# Dual_LPF_Schematic.net
KiCad netlist of a schematic drawn in EAGLE
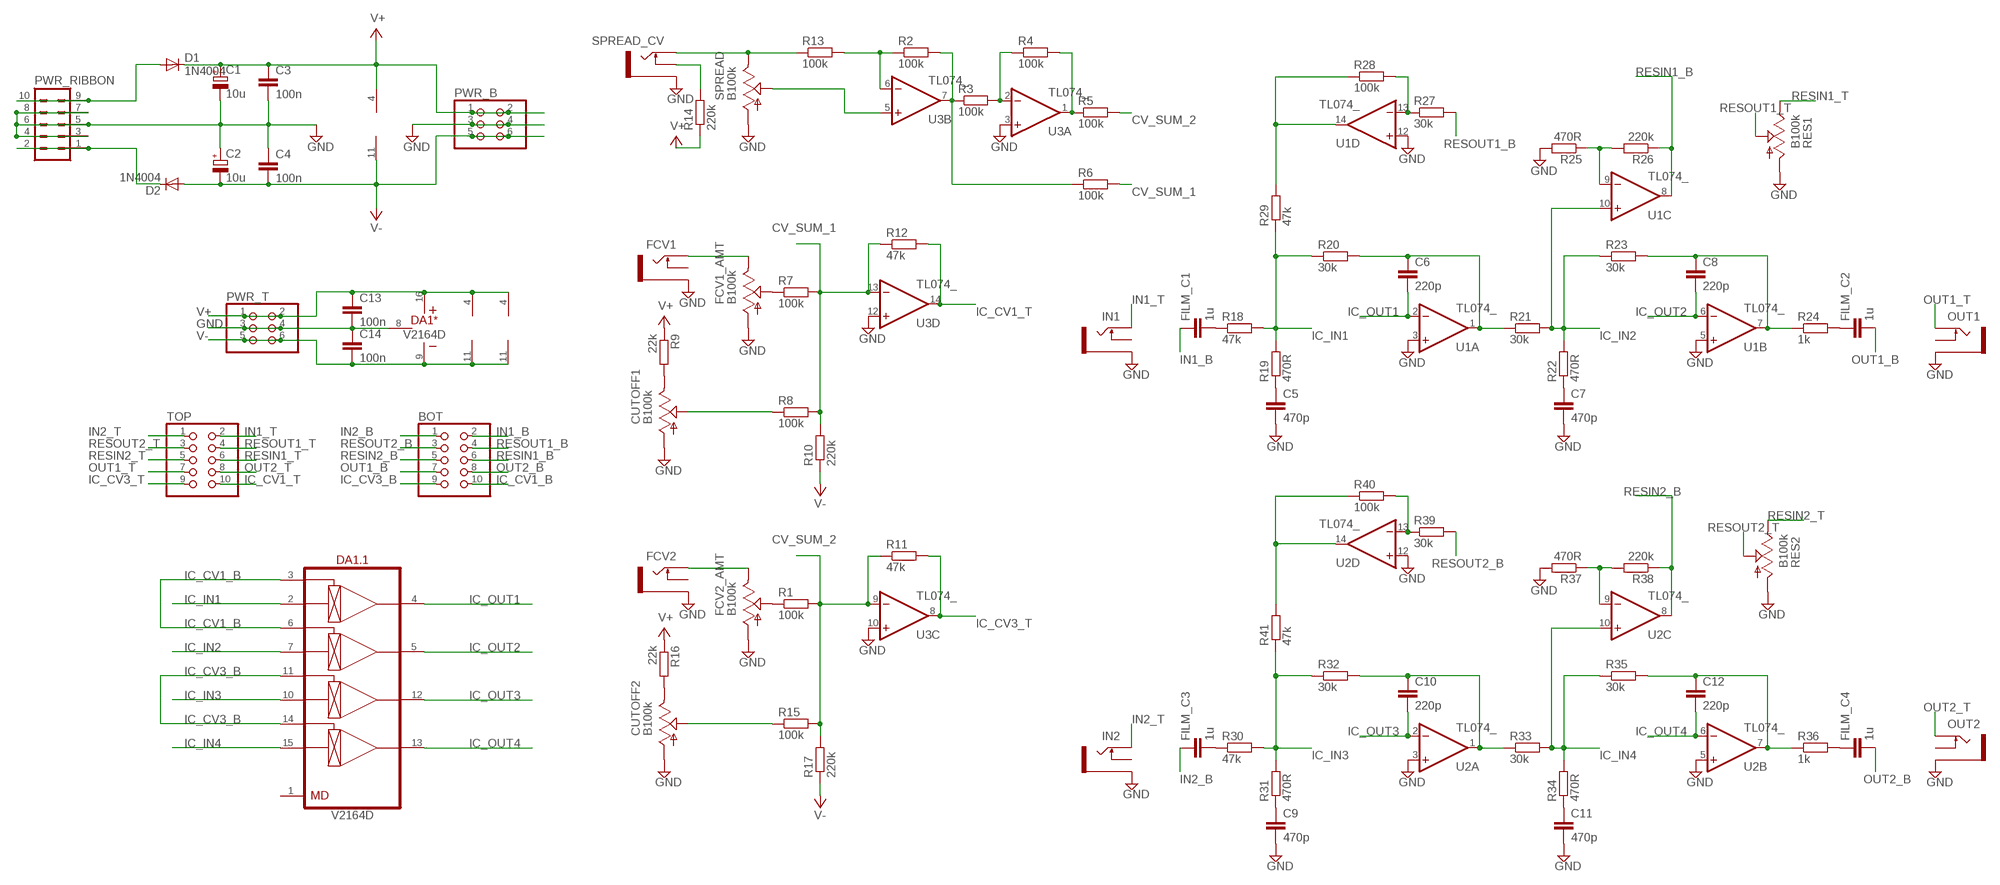
[diagram p0: schematic, sheet 1]

(export (version "E")
  (design (tool "Eeschema 10.0.6"))
  (components
    (comp (ref "BOT")
      (value "PINHD-2X5")
      (footprint "eagle-import:2X05")
      (libsource (lib "eagle-import") (part "PINHD-2X5"))
    )
    (comp (ref "C1")
      (value "10u")
      (footprint "eagle-import:E5-10,5")
      (libsource (lib "eagle-import") (part "CPOL-EUE5-10.5"))
    )
    (comp (ref "C2")
      (value "10u")
      (footprint "eagle-import:E5-10,5")
      (libsource (lib "eagle-import") (part "CPOL-EUE5-10.5"))
    )
    (comp (ref "C3")
      (value "100n")
      (footprint "eagle-import:C050-024X044")
      (libsource (lib "eagle-import") (part "C-EU050-024X044"))
    )
    (comp (ref "C4")
      (value "100n")
      (footprint "eagle-import:C050-024X044")
      (libsource (lib "eagle-import") (part "C-EU050-024X044"))
    )
    (comp (ref "C5")
      (value "470p")
      (footprint "eagle-import:C050-024X044")
      (libsource (lib "eagle-import") (part "C-EU050-024X044"))
    )
    (comp (ref "C6")
      (value "220p")
      (footprint "eagle-import:C050-024X044")
      (libsource (lib "eagle-import") (part "C-EU050-024X044"))
    )
    (comp (ref "C7")
      (value "470p")
      (footprint "eagle-import:C050-024X044")
      (libsource (lib "eagle-import") (part "C-EU050-024X044"))
    )
    (comp (ref "C8")
      (value "220p")
      (footprint "eagle-import:C050-024X044")
      (libsource (lib "eagle-import") (part "C-EU050-024X044"))
    )
    (comp (ref "C9")
      (value "470p")
      (footprint "eagle-import:C050-024X044")
      (libsource (lib "eagle-import") (part "C-EU050-024X044"))
    )
    (comp (ref "C10")
      (value "220p")
      (footprint "eagle-import:C050-024X044")
      (libsource (lib "eagle-import") (part "C-EU050-024X044"))
    )
    (comp (ref "C11")
      (value "470p")
      (footprint "eagle-import:C050-024X044")
      (libsource (lib "eagle-import") (part "C-EU050-024X044"))
    )
    (comp (ref "C12")
      (value "220p")
      (footprint "eagle-import:C050-024X044")
      (libsource (lib "eagle-import") (part "C-EU050-024X044"))
    )
    (comp (ref "C13")
      (value "100n")
      (footprint "eagle-import:C050-024X044")
      (libsource (lib "eagle-import") (part "C-EU050-024X044"))
    )
    (comp (ref "C14")
      (value "100n")
      (footprint "eagle-import:C050-024X044")
      (libsource (lib "eagle-import") (part "C-EU050-024X044"))
    )
    (comp (ref "CUTOFF1")
      (value "B100k")
      (footprint "eagle-import:9MM_SNAP-IN_POT")
      (libsource (lib "eagle-import") (part "9MM_SNAP-IN_POT_"))
    )
    (comp (ref "CUTOFF2")
      (value "B100k")
      (footprint "eagle-import:9MM_SNAP-IN_POT")
      (libsource (lib "eagle-import") (part "9MM_SNAP-IN_POT_"))
    )
    (comp (ref "D1")
      (value "1N4004")
      (footprint "eagle-import:DO41-10")
      (libsource (lib "eagle-import") (part "1N4004"))
    )
    (comp (ref "D2")
      (value "1N4004")
      (footprint "eagle-import:DO41-10")
      (libsource (lib "eagle-import") (part "1N4004"))
    )
    (comp (ref "DA1")
      (value "V2164D")
      (footprint "eagle-import:DIP-16")
      (libsource (lib "eagle-import") (part "V2164D"))
    )
    (comp (ref "FCV1")
      (value "THONKICONNNEW")
      (footprint "eagle-import:WQP-PJ301M-12_JACK")
      (libsource (lib "eagle-import") (part "THONKICONNNEW"))
    )
    (comp (ref "FCV1_AMT")
      (value "B100k")
      (footprint "eagle-import:9MM_SNAP-IN_POT")
      (libsource (lib "eagle-import") (part "9MM_SNAP-IN_POT_"))
    )
    (comp (ref "FCV2")
      (value "THONKICONNNEW")
      (footprint "eagle-import:WQP-PJ301M-12_JACK")
      (libsource (lib "eagle-import") (part "THONKICONNNEW"))
    )
    (comp (ref "FCV2_AMT")
      (value "B100k")
      (footprint "eagle-import:9MM_SNAP-IN_POT")
      (libsource (lib "eagle-import") (part "9MM_SNAP-IN_POT_"))
    )
    (comp (ref "FILM_C1")
      (value "1u")
      (footprint "eagle-import:C050-045X075")
      (libsource (lib "eagle-import") (part "C-EU050-045X075"))
    )
    (comp (ref "FILM_C2")
      (value "1u")
      (footprint "eagle-import:C050-045X075")
      (libsource (lib "eagle-import") (part "C-EU050-045X075"))
    )
    (comp (ref "FILM_C3")
      (value "1u")
      (footprint "eagle-import:C050-045X075")
      (libsource (lib "eagle-import") (part "C-EU050-045X075"))
    )
    (comp (ref "FILM_C4")
      (value "1u")
      (footprint "eagle-import:C050-045X075")
      (libsource (lib "eagle-import") (part "C-EU050-045X075"))
    )
    (comp (ref "IN1")
      (value "THONKICONNNEW")
      (footprint "eagle-import:WQP-PJ301M-12_JACK")
      (libsource (lib "eagle-import") (part "THONKICONNNEW"))
    )
    (comp (ref "IN2")
      (value "THONKICONNNEW")
      (footprint "eagle-import:WQP-PJ301M-12_JACK")
      (libsource (lib "eagle-import") (part "THONKICONNNEW"))
    )
    (comp (ref "OUT1")
      (value "THONKICONNNEW")
      (footprint "eagle-import:WQP-PJ301M-12_JACK")
      (libsource (lib "eagle-import") (part "THONKICONNNEW"))
    )
    (comp (ref "OUT2")
      (value "THONKICONNNEW")
      (footprint "eagle-import:WQP-PJ301M-12_JACK")
      (libsource (lib "eagle-import") (part "THONKICONNNEW"))
    )
    (comp (ref "PWR_B")
      (value "PINHD-2X3")
      (footprint "eagle-import:2X03")
      (libsource (lib "eagle-import") (part "PINHD-2X3"))
    )
    (comp (ref "PWR_RIBBON")
      (value "EURO_POWER_HEADERFAT_PADS")
      (footprint "eagle-import:EURO_PWR_HEADER_FAT")
      (libsource (lib "eagle-import") (part "EURO_POWER_HEADERFAT_PADS"))
    )
    (comp (ref "PWR_T")
      (value "PINHD-2X3")
      (footprint "eagle-import:2X03")
      (libsource (lib "eagle-import") (part "PINHD-2X3"))
    )
    (comp (ref "R1")
      (value "100k")
      (footprint "eagle-import:0207_7")
      (libsource (lib "eagle-import") (part "R-EU_0207/7"))
    )
    (comp (ref "R2")
      (value "100k")
      (footprint "eagle-import:0207_7")
      (libsource (lib "eagle-import") (part "R-EU_0207/7"))
    )
    (comp (ref "R3")
      (value "100k")
      (footprint "eagle-import:0207_7")
      (libsource (lib "eagle-import") (part "R-EU_0207/7"))
    )
    (comp (ref "R4")
      (value "100k")
      (footprint "eagle-import:0207_7")
      (libsource (lib "eagle-import") (part "R-EU_0207/7"))
    )
    (comp (ref "R5")
      (value "100k")
      (footprint "eagle-import:0207_7")
      (libsource (lib "eagle-import") (part "R-EU_0207/7"))
    )
    (comp (ref "R6")
      (value "100k")
      (footprint "eagle-import:0207_7")
      (libsource (lib "eagle-import") (part "R-EU_0207/7"))
    )
    (comp (ref "R7")
      (value "100k")
      (footprint "eagle-import:0207_7")
      (libsource (lib "eagle-import") (part "R-EU_0207/7"))
    )
    (comp (ref "R8")
      (value "100k")
      (footprint "eagle-import:0207_7")
      (libsource (lib "eagle-import") (part "R-EU_0207/7"))
    )
    (comp (ref "R9")
      (value "22k")
      (footprint "eagle-import:0207_7")
      (libsource (lib "eagle-import") (part "R-EU_0207/7"))
    )
    (comp (ref "R10")
      (value "220k")
      (footprint "eagle-import:0207_7")
      (libsource (lib "eagle-import") (part "R-EU_0207/7"))
    )
    (comp (ref "R11")
      (value "47k")
      (footprint "eagle-import:0207_7")
      (libsource (lib "eagle-import") (part "R-EU_0207/7"))
    )
    (comp (ref "R12")
      (value "47k")
      (footprint "eagle-import:0207_7")
      (libsource (lib "eagle-import") (part "R-EU_0207/7"))
    )
    (comp (ref "R13")
      (value "100k")
      (footprint "eagle-import:0207_7")
      (libsource (lib "eagle-import") (part "R-EU_0207/7"))
    )
    (comp (ref "R14")
      (value "220k")
      (footprint "eagle-import:0207_7")
      (libsource (lib "eagle-import") (part "R-EU_0207/7"))
    )
    (comp (ref "R15")
      (value "100k")
      (footprint "eagle-import:0207_7")
      (libsource (lib "eagle-import") (part "R-EU_0207/7"))
    )
    (comp (ref "R16")
      (value "22k")
      (footprint "eagle-import:0207_7")
      (libsource (lib "eagle-import") (part "R-EU_0207/7"))
    )
    (comp (ref "R17")
      (value "220k")
      (footprint "eagle-import:0207_7")
      (libsource (lib "eagle-import") (part "R-EU_0207/7"))
    )
    (comp (ref "R18")
      (value "47k")
      (footprint "eagle-import:0207_7")
      (libsource (lib "eagle-import") (part "R-EU_0207/7"))
    )
    (comp (ref "R19")
      (value "470R")
      (footprint "eagle-import:0207_7")
      (libsource (lib "eagle-import") (part "R-EU_0207/7"))
    )
    (comp (ref "R20")
      (value "30k")
      (footprint "eagle-import:0207_7")
      (libsource (lib "eagle-import") (part "R-EU_0207/7"))
    )
    (comp (ref "R21")
      (value "30k")
      (footprint "eagle-import:0207_7")
      (libsource (lib "eagle-import") (part "R-EU_0207/7"))
    )
    (comp (ref "R22")
      (value "470R")
      (footprint "eagle-import:0207_7")
      (libsource (lib "eagle-import") (part "R-EU_0207/7"))
    )
    (comp (ref "R23")
      (value "30k")
      (footprint "eagle-import:0207_7")
      (libsource (lib "eagle-import") (part "R-EU_0207/7"))
    )
    (comp (ref "R24")
      (value "1k")
      (footprint "eagle-import:0207_7")
      (libsource (lib "eagle-import") (part "R-EU_0207/7"))
    )
    (comp (ref "R25")
      (value "470R")
      (footprint "eagle-import:0207_7")
      (libsource (lib "eagle-import") (part "R-EU_0207/7"))
    )
    (comp (ref "R26")
      (value "220k")
      (footprint "eagle-import:0207_7")
      (libsource (lib "eagle-import") (part "R-EU_0207/7"))
    )
    (comp (ref "R27")
      (value "30k")
      (footprint "eagle-import:0207_7")
      (libsource (lib "eagle-import") (part "R-EU_0207/7"))
    )
    (comp (ref "R28")
      (value "100k")
      (footprint "eagle-import:0207_7")
      (libsource (lib "eagle-import") (part "R-EU_0207/7"))
    )
    (comp (ref "R29")
      (value "47k")
      (footprint "eagle-import:0207_7")
      (libsource (lib "eagle-import") (part "R-EU_0207/7"))
    )
    (comp (ref "R30")
      (value "47k")
      (footprint "eagle-import:0207_7")
      (libsource (lib "eagle-import") (part "R-EU_0207/7"))
    )
    (comp (ref "R31")
      (value "470R")
      (footprint "eagle-import:0207_7")
      (libsource (lib "eagle-import") (part "R-EU_0207/7"))
    )
    (comp (ref "R32")
      (value "30k")
      (footprint "eagle-import:0207_7")
      (libsource (lib "eagle-import") (part "R-EU_0207/7"))
    )
    (comp (ref "R33")
      (value "30k")
      (footprint "eagle-import:0207_7")
      (libsource (lib "eagle-import") (part "R-EU_0207/7"))
    )
    (comp (ref "R34")
      (value "470R")
      (footprint "eagle-import:0207_7")
      (libsource (lib "eagle-import") (part "R-EU_0207/7"))
    )
    (comp (ref "R35")
      (value "30k")
      (footprint "eagle-import:0207_7")
      (libsource (lib "eagle-import") (part "R-EU_0207/7"))
    )
    (comp (ref "R36")
      (value "1k")
      (footprint "eagle-import:0207_7")
      (libsource (lib "eagle-import") (part "R-EU_0207/7"))
    )
    (comp (ref "R37")
      (value "470R")
      (footprint "eagle-import:0207_7")
      (libsource (lib "eagle-import") (part "R-EU_0207/7"))
    )
    (comp (ref "R38")
      (value "220k")
      (footprint "eagle-import:0207_7")
      (libsource (lib "eagle-import") (part "R-EU_0207/7"))
    )
    (comp (ref "R39")
      (value "30k")
      (footprint "eagle-import:0207_7")
      (libsource (lib "eagle-import") (part "R-EU_0207/7"))
    )
    (comp (ref "R40")
      (value "100k")
      (footprint "eagle-import:0207_7")
      (libsource (lib "eagle-import") (part "R-EU_0207/7"))
    )
    (comp (ref "R41")
      (value "47k")
      (footprint "eagle-import:0207_7")
      (libsource (lib "eagle-import") (part "R-EU_0207/7"))
    )
    (comp (ref "RES1")
      (value "B100k")
      (footprint "eagle-import:9MM_SNAP-IN_POT")
      (libsource (lib "eagle-import") (part "9MM_SNAP-IN_POT_"))
    )
    (comp (ref "RES2")
      (value "B100k")
      (footprint "eagle-import:9MM_SNAP-IN_POT")
      (libsource (lib "eagle-import") (part "9MM_SNAP-IN_POT_"))
    )
    (comp (ref "SPREAD")
      (value "B100k")
      (footprint "eagle-import:9MM_SNAP-IN_POT")
      (libsource (lib "eagle-import") (part "9MM_SNAP-IN_POT_"))
    )
    (comp (ref "SPREAD_CV")
      (value "THONKICONNNEW")
      (footprint "eagle-import:WQP-PJ301M-12_JACK")
      (libsource (lib "eagle-import") (part "THONKICONNNEW"))
    )
    (comp (ref "TOP")
      (value "PINHD-2X5")
      (footprint "eagle-import:2X05")
      (libsource (lib "eagle-import") (part "PINHD-2X5"))
    )
    (comp (ref "U1")
      (value "TL074_")
      (footprint "eagle-import:DIL14")
      (libsource (lib "eagle-import") (part "TL074_"))
    )
    (comp (ref "U2")
      (value "TL074_")
      (footprint "eagle-import:DIL14")
      (libsource (lib "eagle-import") (part "TL074_"))
    )
    (comp (ref "U3")
      (value "TL074_")
      (footprint "eagle-import:DIL14")
      (libsource (lib "eagle-import") (part "TL074_"))
    )
  )
  (nets
    (net (code "1") (name "CV_SUM_1") (class "Default")
      (node (ref "R10") (pin "2") (pinfunction "2_2") (pintype "passive"))
      (node (ref "R12") (pin "1") (pinfunction "1_1") (pintype "passive"))
      (node (ref "R6") (pin "2") (pinfunction "2_2") (pintype "passive"))
      (node (ref "R7") (pin "2") (pinfunction "2_2") (pintype "passive"))
      (node (ref "R8") (pin "2") (pinfunction "2_2") (pintype "passive"))
      (node (ref "U3") (pin "13") (pinfunction "-IN_13") (pintype "input"))
    )
    (net (code "2") (name "CV_SUM_2") (class "Default")
      (node (ref "R1") (pin "2") (pinfunction "2_2") (pintype "passive"))
      (node (ref "R11") (pin "1") (pinfunction "1_1") (pintype "passive"))
      (node (ref "R15") (pin "2") (pinfunction "2_2") (pintype "passive"))
      (node (ref "R17") (pin "2") (pinfunction "2_2") (pintype "passive"))
      (node (ref "R5") (pin "2") (pinfunction "2_2") (pintype "passive"))
      (node (ref "U3") (pin "9") (pinfunction "-IN_9") (pintype "input"))
    )
    (net (code "3") (name "GND") (class "Default")
      (node (ref "C1") (pin "-") (pinfunction "-_-") (pintype "passive"))
      (node (ref "C11") (pin "2") (pinfunction "2_2") (pintype "passive"))
      (node (ref "C13") (pin "2") (pinfunction "2_2") (pintype "passive"))
      (node (ref "C14") (pin "1") (pinfunction "1_1") (pintype "passive"))
      (node (ref "C2") (pin "+") (pinfunction "+_+") (pintype "passive"))
      (node (ref "C3") (pin "2") (pinfunction "2_2") (pintype "passive"))
      (node (ref "C4") (pin "1") (pinfunction "1_1") (pintype "passive"))
      (node (ref "C5") (pin "2") (pinfunction "2_2") (pintype "passive"))
      (node (ref "C7") (pin "2") (pinfunction "2_2") (pintype "passive"))
      (node (ref "C9") (pin "2") (pinfunction "2_2") (pintype "passive"))
      (node (ref "CUTOFF1") (pin "1") (pinfunction "A_1") (pintype "passive"))
      (node (ref "CUTOFF2") (pin "1") (pinfunction "A_1") (pintype "passive"))
      (node (ref "DA1") (pin "8") (pinfunction "GND_8") (pintype "power_in"))
      (node (ref "FCV1") (pin "P$3_SLEEVE") (pinfunction "SLEEVE_P$3_SLEEVE") (pintype "passive"))
      (node (ref "FCV1_AMT") (pin "1") (pinfunction "A_1") (pintype "passive"))
      (node (ref "FCV2") (pin "P$3_SLEEVE") (pinfunction "SLEEVE_P$3_SLEEVE") (pintype "passive"))
      (node (ref "FCV2_AMT") (pin "1") (pinfunction "A_1") (pintype "passive"))
      (node (ref "IN1") (pin "P$3_SLEEVE") (pinfunction "SLEEVE_P$3_SLEEVE") (pintype "passive"))
      (node (ref "IN2") (pin "P$3_SLEEVE") (pinfunction "SLEEVE_P$3_SLEEVE") (pintype "passive"))
      (node (ref "OUT1") (pin "P$3_SLEEVE") (pinfunction "SLEEVE_P$3_SLEEVE") (pintype "passive"))
      (node (ref "OUT2") (pin "P$3_SLEEVE") (pinfunction "SLEEVE_P$3_SLEEVE") (pintype "passive"))
      (node (ref "PWR_B") (pin "3") (pinfunction "3_3") (pintype "passive"))
      (node (ref "PWR_B") (pin "4") (pinfunction "4_4") (pintype "passive"))
      (node (ref "PWR_RIBBON") (pin "3") (pinfunction "3_3") (pintype "passive"))
      (node (ref "PWR_RIBBON") (pin "4") (pinfunction "4_4") (pintype "passive"))
      (node (ref "PWR_RIBBON") (pin "5") (pinfunction "5_5") (pintype "passive"))
      (node (ref "PWR_RIBBON") (pin "6") (pinfunction "6_6") (pintype "passive"))
      (node (ref "PWR_RIBBON") (pin "7") (pinfunction "7_7") (pintype "passive"))
      (node (ref "PWR_RIBBON") (pin "8") (pinfunction "8_8") (pintype "passive"))
      (node (ref "PWR_T") (pin "3") (pinfunction "3_3") (pintype "passive"))
      (node (ref "PWR_T") (pin "4") (pinfunction "4_4") (pintype "passive"))
      (node (ref "R25") (pin "2") (pinfunction "2_2") (pintype "passive"))
      (node (ref "R37") (pin "2") (pinfunction "2_2") (pintype "passive"))
      (node (ref "RES1") (pin "1") (pinfunction "A_1") (pintype "passive"))
      (node (ref "RES2") (pin "1") (pinfunction "A_1") (pintype "passive"))
      (node (ref "SPREAD") (pin "1") (pinfunction "A_1") (pintype "passive"))
      (node (ref "SPREAD_CV") (pin "P$3_SLEEVE") (pinfunction "SLEEVE_P$3_SLEEVE") (pintype "passive"))
      (node (ref "U1") (pin "12") (pinfunction "+IN_12") (pintype "input"))
      (node (ref "U1") (pin "3") (pinfunction "+IN_3") (pintype "input"))
      (node (ref "U1") (pin "5") (pinfunction "+IN_5") (pintype "input"))
      (node (ref "U2") (pin "12") (pinfunction "+IN_12") (pintype "input"))
      (node (ref "U2") (pin "3") (pinfunction "+IN_3") (pintype "input"))
      (node (ref "U2") (pin "5") (pinfunction "+IN_5") (pintype "input"))
      (node (ref "U3") (pin "10") (pinfunction "+IN_10") (pintype "input"))
      (node (ref "U3") (pin "12") (pinfunction "+IN_12") (pintype "input"))
      (node (ref "U3") (pin "3") (pinfunction "+IN_3") (pintype "input"))
    )
    (net (code "4") (name "IC_CV1_B") (class "Default")
      (node (ref "BOT") (pin "10") (pinfunction "10_10") (pintype "passive"))
      (node (ref "DA1") (pin "3") (pinfunction "CV1_3") (pintype "input"))
      (node (ref "DA1") (pin "6") (pinfunction "CV2_6") (pintype "input"))
    )
    (net (code "5") (name "IC_CV1_T") (class "Default")
      (node (ref "R12") (pin "2") (pinfunction "2_2") (pintype "passive"))
      (node (ref "TOP") (pin "10") (pinfunction "10_10") (pintype "passive"))
      (node (ref "U3") (pin "14") (pinfunction "OUT_14") (pintype "output"))
    )
    (net (code "6") (name "IC_CV3_B") (class "Default")
      (node (ref "BOT") (pin "9") (pinfunction "9_9") (pintype "passive"))
      (node (ref "DA1") (pin "11") (pinfunction "CV3_11") (pintype "input"))
      (node (ref "DA1") (pin "14") (pinfunction "CV4_14") (pintype "input"))
    )
    (net (code "7") (name "IC_CV3_T") (class "Default")
      (node (ref "R11") (pin "2") (pinfunction "2_2") (pintype "passive"))
      (node (ref "TOP") (pin "9") (pinfunction "9_9") (pintype "passive"))
      (node (ref "U3") (pin "8") (pinfunction "OUT_8") (pintype "output"))
    )
    (net (code "8") (name "IC_IN1") (class "Default")
      (node (ref "DA1") (pin "2") (pinfunction "IN1_2") (pintype "input"))
      (node (ref "R18") (pin "2") (pinfunction "2_2") (pintype "passive"))
      (node (ref "R19") (pin "2") (pinfunction "2_2") (pintype "passive"))
      (node (ref "R20") (pin "1") (pinfunction "1_1") (pintype "passive"))
      (node (ref "R29") (pin "1") (pinfunction "1_1") (pintype "passive"))
    )
    (net (code "9") (name "IC_IN2") (class "Default")
      (node (ref "DA1") (pin "7") (pinfunction "IN2_7") (pintype "input"))
      (node (ref "R21") (pin "2") (pinfunction "2_2") (pintype "passive"))
      (node (ref "R22") (pin "2") (pinfunction "2_2") (pintype "passive"))
      (node (ref "R23") (pin "1") (pinfunction "1_1") (pintype "passive"))
      (node (ref "U1") (pin "10") (pinfunction "+IN_10") (pintype "input"))
    )
    (net (code "10") (name "IC_IN3") (class "Default")
      (node (ref "DA1") (pin "10") (pinfunction "IN3_10") (pintype "input"))
      (node (ref "R30") (pin "2") (pinfunction "2_2") (pintype "passive"))
      (node (ref "R31") (pin "2") (pinfunction "2_2") (pintype "passive"))
      (node (ref "R32") (pin "1") (pinfunction "1_1") (pintype "passive"))
      (node (ref "R41") (pin "1") (pinfunction "1_1") (pintype "passive"))
    )
    (net (code "11") (name "IC_IN4") (class "Default")
      (node (ref "DA1") (pin "15") (pinfunction "IN4_15") (pintype "input"))
      (node (ref "R33") (pin "2") (pinfunction "2_2") (pintype "passive"))
      (node (ref "R34") (pin "2") (pinfunction "2_2") (pintype "passive"))
      (node (ref "R35") (pin "1") (pinfunction "1_1") (pintype "passive"))
      (node (ref "U2") (pin "10") (pinfunction "+IN_10") (pintype "input"))
    )
    (net (code "12") (name "IC_OUT1") (class "Default")
      (node (ref "C6") (pin "2") (pinfunction "2_2") (pintype "passive"))
      (node (ref "DA1") (pin "4") (pinfunction "OUT1_4") (pintype "output"))
      (node (ref "U1") (pin "2") (pinfunction "-IN_2") (pintype "input"))
    )
    (net (code "13") (name "IC_OUT2") (class "Default")
      (node (ref "C8") (pin "2") (pinfunction "2_2") (pintype "passive"))
      (node (ref "DA1") (pin "5") (pinfunction "OUT2_5") (pintype "output"))
      (node (ref "U1") (pin "6") (pinfunction "-IN_6") (pintype "input"))
    )
    (net (code "14") (name "IC_OUT3") (class "Default")
      (node (ref "C10") (pin "2") (pinfunction "2_2") (pintype "passive"))
      (node (ref "DA1") (pin "12") (pinfunction "OUT3_12") (pintype "output"))
      (node (ref "U2") (pin "2") (pinfunction "-IN_2") (pintype "input"))
    )
    (net (code "15") (name "IC_OUT4") (class "Default")
      (node (ref "C12") (pin "2") (pinfunction "2_2") (pintype "passive"))
      (node (ref "DA1") (pin "13") (pinfunction "OUT4_13") (pintype "output"))
      (node (ref "U2") (pin "6") (pinfunction "-IN_6") (pintype "input"))
    )
    (net (code "16") (name "IN1_B") (class "Default")
      (node (ref "BOT") (pin "2") (pinfunction "2_2") (pintype "passive"))
      (node (ref "FILM_C1") (pin "1") (pinfunction "1_1") (pintype "passive"))
    )
    (net (code "17") (name "IN1_T") (class "Default")
      (node (ref "IN1") (pin "P$1_TIP") (pinfunction "TIP_P$1_TIP") (pintype "passive"))
      (node (ref "TOP") (pin "2") (pinfunction "2_2") (pintype "passive"))
    )
    (net (code "18") (name "IN2_B") (class "Default")
      (node (ref "BOT") (pin "1") (pinfunction "1_1") (pintype "passive"))
      (node (ref "FILM_C3") (pin "1") (pinfunction "1_1") (pintype "passive"))
    )
    (net (code "19") (name "IN2_T") (class "Default")
      (node (ref "IN2") (pin "P$1_TIP") (pinfunction "TIP_P$1_TIP") (pintype "passive"))
      (node (ref "TOP") (pin "1") (pinfunction "1_1") (pintype "passive"))
    )
    (net (code "20") (name "Net-(C5-Pad1)") (class "Default")
      (node (ref "C5") (pin "1") (pinfunction "1_1") (pintype "passive"))
      (node (ref "R19") (pin "1") (pinfunction "1_1") (pintype "passive"))
    )
    (net (code "21") (name "Net-(C7-Pad1)") (class "Default")
      (node (ref "C7") (pin "1") (pinfunction "1_1") (pintype "passive"))
      (node (ref "R22") (pin "1") (pinfunction "1_1") (pintype "passive"))
    )
    (net (code "22") (name "Net-(C9-Pad1)") (class "Default")
      (node (ref "C9") (pin "1") (pinfunction "1_1") (pintype "passive"))
      (node (ref "R31") (pin "1") (pinfunction "1_1") (pintype "passive"))
    )
    (net (code "23") (name "Net-(C11-Pad1)") (class "Default")
      (node (ref "C11") (pin "1") (pinfunction "1_1") (pintype "passive"))
      (node (ref "R34") (pin "1") (pinfunction "1_1") (pintype "passive"))
    )
    (net (code "24") (name "Net-(CUTOFF1-E)") (class "Default")
      (node (ref "CUTOFF1") (pin "3") (pinfunction "E_3") (pintype "passive"))
      (node (ref "R9") (pin "2") (pinfunction "2_2") (pintype "passive"))
    )
    (net (code "25") (name "Net-(CUTOFF1-S)") (class "Default")
      (node (ref "CUTOFF1") (pin "2") (pinfunction "S_2") (pintype "passive"))
      (node (ref "R8") (pin "1") (pinfunction "1_1") (pintype "passive"))
    )
    (net (code "26") (name "Net-(CUTOFF2-E)") (class "Default")
      (node (ref "CUTOFF2") (pin "3") (pinfunction "E_3") (pintype "passive"))
      (node (ref "R16") (pin "2") (pinfunction "2_2") (pintype "passive"))
    )
    (net (code "27") (name "Net-(CUTOFF2-S)") (class "Default")
      (node (ref "CUTOFF2") (pin "2") (pinfunction "S_2") (pintype "passive"))
      (node (ref "R15") (pin "1") (pinfunction "1_1") (pintype "passive"))
    )
    (net (code "28") (name "Net-(D1-PadA)") (class "Default")
      (node (ref "D1") (pin "A") (pinfunction "A_A") (pintype "passive"))
      (node (ref "PWR_RIBBON") (pin "10") (pinfunction "10_10") (pintype "passive"))
      (node (ref "PWR_RIBBON") (pin "9") (pinfunction "9_9") (pintype "passive"))
    )
    (net (code "29") (name "Net-(D2-PadC)") (class "Default")
      (node (ref "D2") (pin "C") (pinfunction "C_C") (pintype "passive"))
      (node (ref "PWR_RIBBON") (pin "1") (pinfunction "1_1") (pintype "passive"))
      (node (ref "PWR_RIBBON") (pin "2") (pinfunction "2_2") (pintype "passive"))
    )
    (net (code "30") (name "Net-(FCV1-TIP)") (class "Default")
      (node (ref "FCV1") (pin "P$1_TIP") (pinfunction "TIP_P$1_TIP") (pintype "passive"))
      (node (ref "FCV1_AMT") (pin "3") (pinfunction "E_3") (pintype "passive"))
    )
    (net (code "31") (name "Net-(FCV1_AMT-S)") (class "Default")
      (node (ref "FCV1_AMT") (pin "2") (pinfunction "S_2") (pintype "passive"))
      (node (ref "R7") (pin "1") (pinfunction "1_1") (pintype "passive"))
    )
    (net (code "32") (name "Net-(FCV2-TIP)") (class "Default")
      (node (ref "FCV2") (pin "P$1_TIP") (pinfunction "TIP_P$1_TIP") (pintype "passive"))
      (node (ref "FCV2_AMT") (pin "3") (pinfunction "E_3") (pintype "passive"))
    )
    (net (code "33") (name "Net-(FCV2_AMT-S)") (class "Default")
      (node (ref "FCV2_AMT") (pin "2") (pinfunction "S_2") (pintype "passive"))
      (node (ref "R1") (pin "1") (pinfunction "1_1") (pintype "passive"))
    )
    (net (code "34") (name "Net-(FILM_C1-Pad2)") (class "Default")
      (node (ref "FILM_C1") (pin "2") (pinfunction "2_2") (pintype "passive"))
      (node (ref "R18") (pin "1") (pinfunction "1_1") (pintype "passive"))
    )
    (net (code "35") (name "Net-(FILM_C2-Pad1)") (class "Default")
      (node (ref "FILM_C2") (pin "1") (pinfunction "1_1") (pintype "passive"))
      (node (ref "R24") (pin "2") (pinfunction "2_2") (pintype "passive"))
    )
    (net (code "36") (name "Net-(FILM_C3-Pad2)") (class "Default")
      (node (ref "FILM_C3") (pin "2") (pinfunction "2_2") (pintype "passive"))
      (node (ref "R30") (pin "1") (pinfunction "1_1") (pintype "passive"))
    )
    (net (code "37") (name "Net-(FILM_C4-Pad1)") (class "Default")
      (node (ref "FILM_C4") (pin "1") (pinfunction "1_1") (pintype "passive"))
      (node (ref "R36") (pin "2") (pinfunction "2_2") (pintype "passive"))
    )
    (net (code "38") (name "Net-(SPREAD-E)") (class "Default")
      (node (ref "R13") (pin "1") (pinfunction "1_1") (pintype "passive"))
      (node (ref "SPREAD") (pin "3") (pinfunction "E_3") (pintype "passive"))
      (node (ref "SPREAD_CV") (pin "P$1_TIP") (pinfunction "TIP_P$1_TIP") (pintype "passive"))
    )
    (net (code "39") (name "Net-(SPREAD-S)") (class "Default")
      (node (ref "SPREAD") (pin "2") (pinfunction "S_2") (pintype "passive"))
      (node (ref "U3") (pin "5") (pinfunction "+IN_5") (pintype "input"))
    )
    (net (code "40") (name "Net-(SPREAD_CV-SWITCH)") (class "Default")
      (node (ref "R14") (pin "2") (pinfunction "2_2") (pintype "passive"))
      (node (ref "SPREAD_CV") (pin "P$2_SWITCH") (pinfunction "SWITCH_P$2_SWITCH") (pintype "passive"))
    )
    (net (code "41") (name "Net-(U1A-OUT)") (class "Default")
      (node (ref "C6") (pin "1") (pinfunction "1_1") (pintype "passive"))
      (node (ref "R20") (pin "2") (pinfunction "2_2") (pintype "passive"))
      (node (ref "R21") (pin "1") (pinfunction "1_1") (pintype "passive"))
      (node (ref "U1") (pin "1") (pinfunction "OUT_1") (pintype "output"))
    )
    (net (code "42") (name "Net-(U1B-OUT)") (class "Default")
      (node (ref "C8") (pin "1") (pinfunction "1_1") (pintype "passive"))
      (node (ref "R23") (pin "2") (pinfunction "2_2") (pintype "passive"))
      (node (ref "R24") (pin "1") (pinfunction "1_1") (pintype "passive"))
      (node (ref "U1") (pin "7") (pinfunction "OUT_7") (pintype "output"))
    )
    (net (code "43") (name "Net-(U1C--IN)") (class "Default")
      (node (ref "R25") (pin "1") (pinfunction "1_1") (pintype "passive"))
      (node (ref "R26") (pin "2") (pinfunction "2_2") (pintype "passive"))
      (node (ref "U1") (pin "9") (pinfunction "-IN_9") (pintype "input"))
    )
    (net (code "44") (name "Net-(U1D--IN)") (class "Default")
      (node (ref "R27") (pin "1") (pinfunction "1_1") (pintype "passive"))
      (node (ref "R28") (pin "2") (pinfunction "2_2") (pintype "passive"))
      (node (ref "U1") (pin "13") (pinfunction "-IN_13") (pintype "input"))
    )
    (net (code "45") (name "Net-(U1D-OUT)") (class "Default")
      (node (ref "R28") (pin "1") (pinfunction "1_1") (pintype "passive"))
      (node (ref "R29") (pin "2") (pinfunction "2_2") (pintype "passive"))
      (node (ref "U1") (pin "14") (pinfunction "OUT_14") (pintype "output"))
    )
    (net (code "46") (name "Net-(U2A-OUT)") (class "Default")
      (node (ref "C10") (pin "1") (pinfunction "1_1") (pintype "passive"))
      (node (ref "R32") (pin "2") (pinfunction "2_2") (pintype "passive"))
      (node (ref "R33") (pin "1") (pinfunction "1_1") (pintype "passive"))
      (node (ref "U2") (pin "1") (pinfunction "OUT_1") (pintype "output"))
    )
    (net (code "47") (name "Net-(U2B-OUT)") (class "Default")
      (node (ref "C12") (pin "1") (pinfunction "1_1") (pintype "passive"))
      (node (ref "R35") (pin "2") (pinfunction "2_2") (pintype "passive"))
      (node (ref "R36") (pin "1") (pinfunction "1_1") (pintype "passive"))
      (node (ref "U2") (pin "7") (pinfunction "OUT_7") (pintype "output"))
    )
    (net (code "48") (name "Net-(U2C--IN)") (class "Default")
      (node (ref "R37") (pin "1") (pinfunction "1_1") (pintype "passive"))
      (node (ref "R38") (pin "2") (pinfunction "2_2") (pintype "passive"))
      (node (ref "U2") (pin "9") (pinfunction "-IN_9") (pintype "input"))
    )
    (net (code "49") (name "Net-(U2D--IN)") (class "Default")
      (node (ref "R39") (pin "1") (pinfunction "1_1") (pintype "passive"))
      (node (ref "R40") (pin "2") (pinfunction "2_2") (pintype "passive"))
      (node (ref "U2") (pin "13") (pinfunction "-IN_13") (pintype "input"))
    )
    (net (code "50") (name "Net-(U2D-OUT)") (class "Default")
      (node (ref "R40") (pin "1") (pinfunction "1_1") (pintype "passive"))
      (node (ref "R41") (pin "2") (pinfunction "2_2") (pintype "passive"))
      (node (ref "U2") (pin "14") (pinfunction "OUT_14") (pintype "output"))
    )
    (net (code "51") (name "Net-(U3A--IN)") (class "Default")
      (node (ref "R3") (pin "2") (pinfunction "2_2") (pintype "passive"))
      (node (ref "R4") (pin "1") (pinfunction "1_1") (pintype "passive"))
      (node (ref "U3") (pin "2") (pinfunction "-IN_2") (pintype "input"))
    )
    (net (code "52") (name "Net-(U3A-OUT)") (class "Default")
      (node (ref "R4") (pin "2") (pinfunction "2_2") (pintype "passive"))
      (node (ref "R5") (pin "1") (pinfunction "1_1") (pintype "passive"))
      (node (ref "U3") (pin "1") (pinfunction "OUT_1") (pintype "output"))
    )
    (net (code "53") (name "Net-(U3B--IN)") (class "Default")
      (node (ref "R13") (pin "2") (pinfunction "2_2") (pintype "passive"))
      (node (ref "R2") (pin "1") (pinfunction "1_1") (pintype "passive"))
      (node (ref "U3") (pin "6") (pinfunction "-IN_6") (pintype "input"))
    )
    (net (code "54") (name "Net-(U3B-OUT)") (class "Default")
      (node (ref "R2") (pin "2") (pinfunction "2_2") (pintype "passive"))
      (node (ref "R3") (pin "1") (pinfunction "1_1") (pintype "passive"))
      (node (ref "R6") (pin "1") (pinfunction "1_1") (pintype "passive"))
      (node (ref "U3") (pin "7") (pinfunction "OUT_7") (pintype "output"))
    )
    (net (code "55") (name "OUT1_B") (class "Default")
      (node (ref "BOT") (pin "7") (pinfunction "7_7") (pintype "passive"))
      (node (ref "FILM_C2") (pin "2") (pinfunction "2_2") (pintype "passive"))
    )
    (net (code "56") (name "OUT1_T") (class "Default")
      (node (ref "OUT1") (pin "P$1_TIP") (pinfunction "TIP_P$1_TIP") (pintype "passive"))
      (node (ref "TOP") (pin "7") (pinfunction "7_7") (pintype "passive"))
    )
    (net (code "57") (name "OUT2_B") (class "Default")
      (node (ref "BOT") (pin "8") (pinfunction "8_8") (pintype "passive"))
      (node (ref "FILM_C4") (pin "2") (pinfunction "2_2") (pintype "passive"))
    )
    (net (code "58") (name "OUT2_T") (class "Default")
      (node (ref "OUT2") (pin "P$1_TIP") (pinfunction "TIP_P$1_TIP") (pintype "passive"))
      (node (ref "TOP") (pin "8") (pinfunction "8_8") (pintype "passive"))
    )
    (net (code "59") (name "RESIN1_B") (class "Default")
      (node (ref "BOT") (pin "6") (pinfunction "6_6") (pintype "passive"))
      (node (ref "R26") (pin "1") (pinfunction "1_1") (pintype "passive"))
      (node (ref "U1") (pin "8") (pinfunction "OUT_8") (pintype "output"))
    )
    (net (code "60") (name "RESIN1_T") (class "Default")
      (node (ref "RES1") (pin "3") (pinfunction "E_3") (pintype "passive"))
      (node (ref "TOP") (pin "6") (pinfunction "6_6") (pintype "passive"))
    )
    (net (code "61") (name "RESIN2_B") (class "Default")
      (node (ref "BOT") (pin "5") (pinfunction "5_5") (pintype "passive"))
      (node (ref "R38") (pin "1") (pinfunction "1_1") (pintype "passive"))
      (node (ref "U2") (pin "8") (pinfunction "OUT_8") (pintype "output"))
    )
    (net (code "62") (name "RESIN2_T") (class "Default")
      (node (ref "RES2") (pin "3") (pinfunction "E_3") (pintype "passive"))
      (node (ref "TOP") (pin "5") (pinfunction "5_5") (pintype "passive"))
    )
    (net (code "63") (name "RESOUT1_B") (class "Default")
      (node (ref "BOT") (pin "4") (pinfunction "4_4") (pintype "passive"))
      (node (ref "R27") (pin "2") (pinfunction "2_2") (pintype "passive"))
    )
    (net (code "64") (name "RESOUT1_T") (class "Default")
      (node (ref "RES1") (pin "2") (pinfunction "S_2") (pintype "passive"))
      (node (ref "TOP") (pin "4") (pinfunction "4_4") (pintype "passive"))
    )
    (net (code "65") (name "RESOUT2_B") (class "Default")
      (node (ref "BOT") (pin "3") (pinfunction "3_3") (pintype "passive"))
      (node (ref "R39") (pin "2") (pinfunction "2_2") (pintype "passive"))
    )
    (net (code "66") (name "RESOUT2_T") (class "Default")
      (node (ref "RES2") (pin "2") (pinfunction "S_2") (pintype "passive"))
      (node (ref "TOP") (pin "3") (pinfunction "3_3") (pintype "passive"))
    )
    (net (code "67") (name "V+") (class "Default")
      (node (ref "C1") (pin "+") (pinfunction "+_+") (pintype "passive"))
      (node (ref "C13") (pin "1") (pinfunction "1_1") (pintype "passive"))
      (node (ref "C3") (pin "1") (pinfunction "1_1") (pintype "passive"))
      (node (ref "D1") (pin "C") (pinfunction "C_C") (pintype "passive"))
      (node (ref "DA1") (pin "16") (pinfunction "V+_16") (pintype "power_in"))
      (node (ref "PWR_B") (pin "1") (pinfunction "1_1") (pintype "passive"))
      (node (ref "PWR_B") (pin "2") (pinfunction "2_2") (pintype "passive"))
      (node (ref "PWR_T") (pin "1") (pinfunction "1_1") (pintype "passive"))
      (node (ref "PWR_T") (pin "2") (pinfunction "2_2") (pintype "passive"))
      (node (ref "R14") (pin "1") (pinfunction "1_1") (pintype "passive"))
      (node (ref "R16") (pin "1") (pinfunction "1_1") (pintype "passive"))
      (node (ref "R9") (pin "1") (pinfunction "1_1") (pintype "passive"))
      (node (ref "U1") (pin "4") (pinfunction "V+_4") (pintype "power_in"))
      (node (ref "U2") (pin "4") (pinfunction "V+_4") (pintype "power_in"))
      (node (ref "U3") (pin "4") (pinfunction "V+_4") (pintype "power_in"))
    )
    (net (code "68") (name "V-") (class "Default")
      (node (ref "C14") (pin "2") (pinfunction "2_2") (pintype "passive"))
      (node (ref "C2") (pin "-") (pinfunction "-_-") (pintype "passive"))
      (node (ref "C4") (pin "2") (pinfunction "2_2") (pintype "passive"))
      (node (ref "D2") (pin "A") (pinfunction "A_A") (pintype "passive"))
      (node (ref "DA1") (pin "9") (pinfunction "V-_9") (pintype "power_in"))
      (node (ref "PWR_B") (pin "5") (pinfunction "5_5") (pintype "passive"))
      (node (ref "PWR_B") (pin "6") (pinfunction "6_6") (pintype "passive"))
      (node (ref "PWR_T") (pin "5") (pinfunction "5_5") (pintype "passive"))
      (node (ref "PWR_T") (pin "6") (pinfunction "6_6") (pintype "passive"))
      (node (ref "R10") (pin "1") (pinfunction "1_1") (pintype "passive"))
      (node (ref "R17") (pin "1") (pinfunction "1_1") (pintype "passive"))
      (node (ref "U1") (pin "11") (pinfunction "V-_11") (pintype "power_in"))
      (node (ref "U2") (pin "11") (pinfunction "V-_11") (pintype "power_in"))
      (node (ref "U3") (pin "11") (pinfunction "V-_11") (pintype "power_in"))
    )
    (net (code "69") (name "unconnected-(DA1B-MD-Pad1)") (class "Default")
      (node (ref "DA1") (pin "1") (pinfunction "MD_1") (pintype "output"))
    )
    (net (code "70") (name "unconnected-(FCV1-SWITCH-PadP$2_SWITCH)") (class "Default")
      (node (ref "FCV1") (pin "P$2_SWITCH") (pinfunction "SWITCH_P$2_SWITCH") (pintype "passive"))
    )
    (net (code "71") (name "unconnected-(FCV2-SWITCH-PadP$2_SWITCH)") (class "Default")
      (node (ref "FCV2") (pin "P$2_SWITCH") (pinfunction "SWITCH_P$2_SWITCH") (pintype "passive"))
    )
    (net (code "72") (name "unconnected-(IN1-SWITCH-PadP$2_SWITCH)") (class "Default")
      (node (ref "IN1") (pin "P$2_SWITCH") (pinfunction "SWITCH_P$2_SWITCH") (pintype "passive"))
    )
    (net (code "73") (name "unconnected-(IN2-SWITCH-PadP$2_SWITCH)") (class "Default")
      (node (ref "IN2") (pin "P$2_SWITCH") (pinfunction "SWITCH_P$2_SWITCH") (pintype "passive"))
    )
    (net (code "74") (name "unconnected-(OUT1-SWITCH-PadP$2_SWITCH)") (class "Default")
      (node (ref "OUT1") (pin "P$2_SWITCH") (pinfunction "SWITCH_P$2_SWITCH") (pintype "passive"))
    )
    (net (code "75") (name "unconnected-(OUT2-SWITCH-PadP$2_SWITCH)") (class "Default")
      (node (ref "OUT2") (pin "P$2_SWITCH") (pinfunction "SWITCH_P$2_SWITCH") (pintype "passive"))
    )
  )
)
